# NanoFury16.net
KiCad netlist of a schematic drawn in Altium Designer
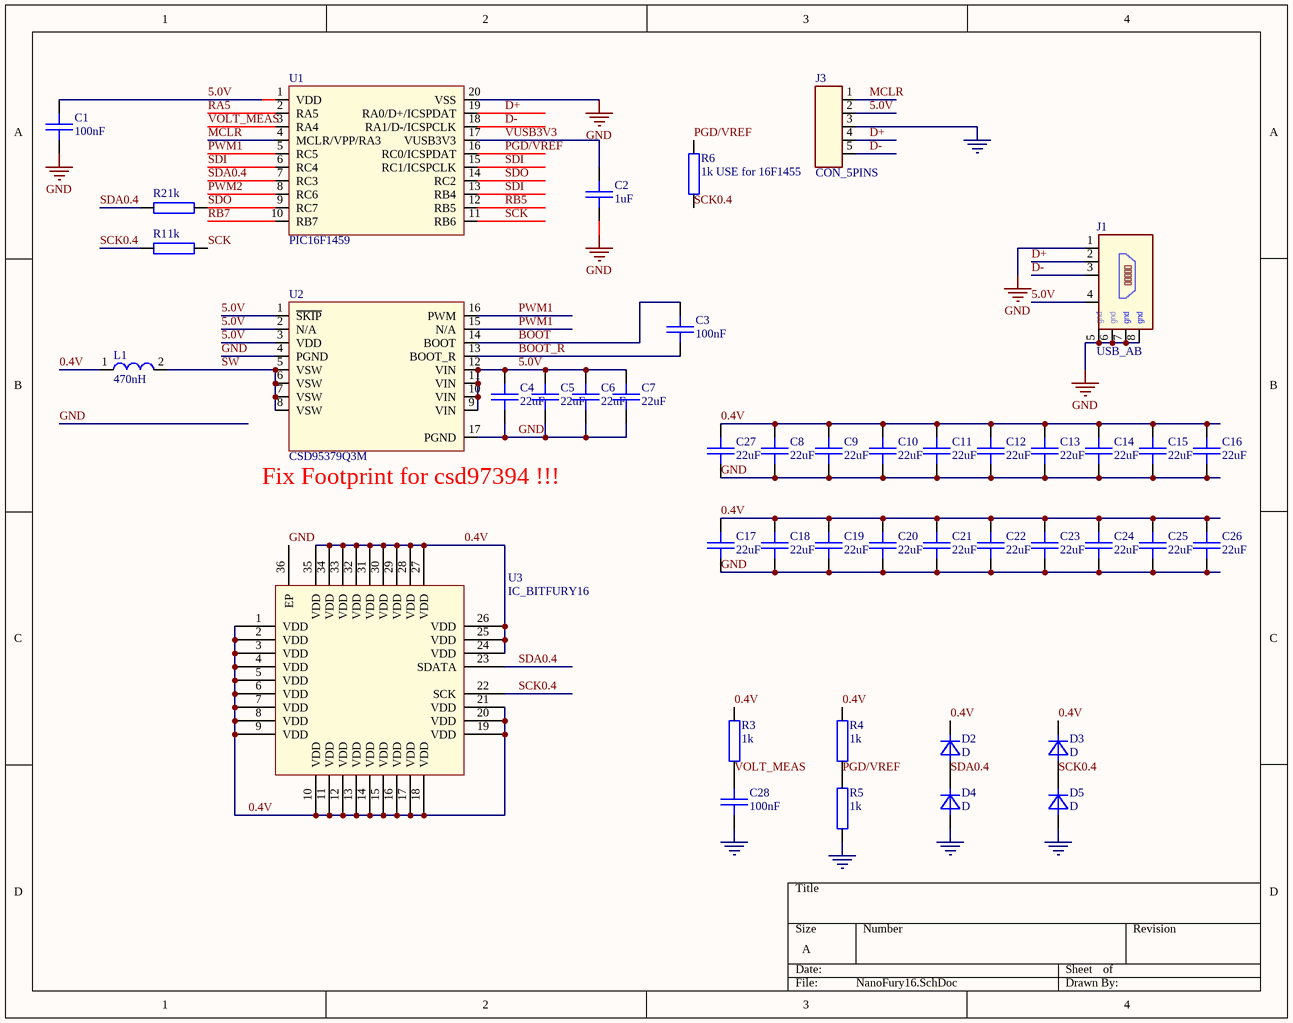
[diagram p0: NanoFury16.SchDoc]

(export (version "E")
  (design (tool "Eeschema 10.0.6"))
  (components
    (comp (ref "C1") (value "100nF") (footprint "SMD_0603_CAPC1608X95N") (libsource (lib "DLV") (part "C")))
    (comp (ref "C2") (value "1uF") (footprint "SMD_0603_CAPC1608X95N") (libsource (lib "DLV") (part "C")))
    (comp (ref "C3") (value "100nF") (footprint "SMD_0603_CAPC1608X95N") (libsource (lib "DLV") (part "C")))
    (comp (ref "C4") (value "22uF") (footprint "SMD_0805_CAPC2012X95N") (libsource (lib "DLV") (part "C")))
    (comp (ref "C5") (value "22uF") (footprint "SMD_0805_CAPC2012X95N") (libsource (lib "DLV") (part "C")))
    (comp (ref "C6") (value "22uF") (footprint "SMD_0805_CAPC2012X95N") (libsource (lib "DLV") (part "C")))
    (comp (ref "C7") (value "22uF") (footprint "SMD_0805_CAPC2012X95N") (libsource (lib "DLV") (part "C")))
    (comp (ref "C8") (value "22uF") (footprint "SMD_0805_CAPC2012X95N") (libsource (lib "DLV") (part "C")))
    (comp (ref "C9") (value "22uF") (footprint "SMD_0805_CAPC2012X95N") (libsource (lib "DLV") (part "C")))
    (comp (ref "C10") (value "22uF") (footprint "SMD_0805_CAPC2012X95N") (libsource (lib "DLV") (part "C")))
    (comp (ref "C11") (value "22uF") (footprint "SMD_0805_CAPC2012X95N") (libsource (lib "DLV") (part "C")))
    (comp (ref "C12") (value "22uF") (footprint "SMD_0805_CAPC2012X95N") (libsource (lib "DLV") (part "C")))
    (comp (ref "C13") (value "22uF") (footprint "SMD_0805_CAPC2012X95N") (libsource (lib "DLV") (part "C")))
    (comp (ref "C14") (value "22uF") (footprint "SMD_0805_CAPC2012X95N") (libsource (lib "DLV") (part "C")))
    (comp (ref "C15") (value "22uF") (footprint "SMD_0805_CAPC2012X95N") (libsource (lib "DLV") (part "C")))
    (comp (ref "C16") (value "22uF") (footprint "SMD_0805_CAPC2012X95N") (libsource (lib "DLV") (part "C")))
    (comp (ref "C17") (value "22uF") (footprint "SMD_0805_CAPC2012X95N") (libsource (lib "DLV") (part "C")))
    (comp (ref "C18") (value "22uF") (footprint "SMD_0805_CAPC2012X95N") (libsource (lib "DLV") (part "C")))
    (comp (ref "C19") (value "22uF") (footprint "SMD_0805_CAPC2012X95N") (libsource (lib "DLV") (part "C")))
    (comp (ref "C20") (value "22uF") (footprint "SMD_0805_CAPC2012X95N") (libsource (lib "DLV") (part "C")))
    (comp (ref "C21") (value "22uF") (footprint "SMD_0805_CAPC2012X95N") (libsource (lib "DLV") (part "C")))
    (comp (ref "C22") (value "22uF") (footprint "SMD_0805_CAPC2012X95N") (libsource (lib "DLV") (part "C")))
    (comp (ref "C23") (value "22uF") (footprint "SMD_0805_CAPC2012X95N") (libsource (lib "DLV") (part "C")))
    (comp (ref "C24") (value "22uF") (footprint "SMD_0805_CAPC2012X95N") (libsource (lib "DLV") (part "C")))
    (comp (ref "C25") (value "22uF") (footprint "SMD_0805_CAPC2012X95N") (libsource (lib "DLV") (part "C")))
    (comp (ref "C26") (value "22uF") (footprint "SMD_0805_CAPC2012X95N") (libsource (lib "DLV") (part "C")))
    (comp (ref "C27") (value "22uF") (footprint "SMD_0805_CAPC2012X95N") (libsource (lib "DLV") (part "C")))
    (comp (ref "C28") (value "100nF") (footprint "SMD_0603_CAPC1608X95N") (libsource (lib "DLV") (part "C")))
    (comp (ref "D2") (value "D") (footprint "SMD_SOD523_SOD1608X65N") (libsource (lib "DLV") (part "D")))
    (comp (ref "D3") (value "D") (footprint "SMD_SOD523_SOD1608X65N") (libsource (lib "DLV") (part "D")))
    (comp (ref "D4") (value "D") (footprint "SMD_SOD523_SOD1608X65N") (libsource (lib "DLV") (part "D")))
    (comp (ref "D5") (value "D") (footprint "SMD_SOD523_SOD1608X65N") (libsource (lib "DLV") (part "D")))
    (comp (ref "J1")
      (value "USB_AB")
      (footprint "PTH_CON_USB_FCI-87520-0010B-LF - MALE SMD PTH")
      (libsource (lib "DLV") (part "CON_USB_AB"))
    )
    (comp (ref "J3") (value "CON_5PINS") (footprint "SIP5 - PGM") (libsource (lib "DLV") (part "CON_5PINS")))
    (comp (ref "L1") (value "470nH") (footprint "SMD_INDM720X665X300") (libsource (lib "DLV") (part "L")))
    (comp (ref "R1") (value "1k") (footprint "SMD_0603_RESC1608X55N") (libsource (lib "DLV") (part "R")))
    (comp (ref "R2") (value "1k") (footprint "SMD_0603_RESC1608X55N") (libsource (lib "DLV") (part "R")))
    (comp (ref "R3") (value "1k") (footprint "SMD_0603_RESC1608X55N") (libsource (lib "DLV") (part "R")))
    (comp (ref "R4") (value "1k") (footprint "SMD_0603_RESC1608X55N") (libsource (lib "DLV") (part "R")))
    (comp (ref "R5") (value "1k") (footprint "SMD_0603_RESC1608X55N") (libsource (lib "DLV") (part "R")))
    (comp (ref "R6")
      (value "1k USE for 16F1455")
      (footprint "SMD_0603_RESC1608X55N")
      (libsource (lib "DLV") (part "R"))
    )
    (comp (ref "U1")
      (value "PIC16F1459")
      (footprint "SMD_SOP65P640X110-20N")
      (libsource (lib "DLV") (part "IC_PIC16F1459"))
    )
    (comp (ref "U2")
      (value "CSD95379Q3M")
      (footprint "SMD_SON50P340X340X80-21N - VSON10")
      (description "Texas Instrumendts Buck Boost DC-DC")
      (libsource (lib "DLV") (part "IC_CSD95379Q3M"))
    )
    (comp (ref "U3")
      (value "IC_BITFURY16")
      (footprint "SMD_QFN65P600X600X100-36AN")
      (description "BitFury 2016 16 nm")
      (libsource (lib "DLV") (part "IC_BITFURY16"))
    )
  )
  (nets
    (net (code "1") (name "/0.4V") (class "Default")
      (node (ref "C10") (pin "1") (pinfunction "1_1") (pintype "passive"))
      (node (ref "C11") (pin "1") (pinfunction "1_1") (pintype "passive"))
      (node (ref "C12") (pin "1") (pinfunction "1_1") (pintype "passive"))
      (node (ref "C13") (pin "1") (pinfunction "1_1") (pintype "passive"))
      (node (ref "C14") (pin "1") (pinfunction "1_1") (pintype "passive"))
      (node (ref "C15") (pin "1") (pinfunction "1_1") (pintype "passive"))
      (node (ref "C16") (pin "1") (pinfunction "1_1") (pintype "passive"))
      (node (ref "C17") (pin "1") (pinfunction "1_1") (pintype "passive"))
      (node (ref "C18") (pin "1") (pinfunction "1_1") (pintype "passive"))
      (node (ref "C19") (pin "1") (pinfunction "1_1") (pintype "passive"))
      (node (ref "C20") (pin "1") (pinfunction "1_1") (pintype "passive"))
      (node (ref "C21") (pin "1") (pinfunction "1_1") (pintype "passive"))
      (node (ref "C22") (pin "1") (pinfunction "1_1") (pintype "passive"))
      (node (ref "C23") (pin "1") (pinfunction "1_1") (pintype "passive"))
      (node (ref "C24") (pin "1") (pinfunction "1_1") (pintype "passive"))
      (node (ref "C25") (pin "1") (pinfunction "1_1") (pintype "passive"))
      (node (ref "C26") (pin "1") (pinfunction "1_1") (pintype "passive"))
      (node (ref "C27") (pin "1") (pinfunction "1_1") (pintype "passive"))
      (node (ref "C8") (pin "1") (pinfunction "1_1") (pintype "passive"))
      (node (ref "C9") (pin "1") (pinfunction "1_1") (pintype "passive"))
      (node (ref "D2") (pin "1") (pinfunction "C_1") (pintype "passive"))
      (node (ref "D3") (pin "1") (pinfunction "C_1") (pintype "passive"))
      (node (ref "L1") (pin "1") (pinfunction "1_1") (pintype "passive"))
      (node (ref "R3") (pin "1") (pinfunction "1_1") (pintype "passive"))
      (node (ref "R4") (pin "1") (pinfunction "1_1") (pintype "passive"))
      (node (ref "U3") (pin "1") (pinfunction "VDD_1") (pintype "passive"))
      (node (ref "U3") (pin "10") (pinfunction "VDD_10") (pintype "passive"))
      (node (ref "U3") (pin "11") (pinfunction "VDD_11") (pintype "passive"))
      (node (ref "U3") (pin "12") (pinfunction "VDD_12") (pintype "passive"))
      (node (ref "U3") (pin "13") (pinfunction "VDD_13") (pintype "passive"))
      (node (ref "U3") (pin "14") (pinfunction "VDD_14") (pintype "passive"))
      (node (ref "U3") (pin "15") (pinfunction "VDD_15") (pintype "passive"))
      (node (ref "U3") (pin "16") (pinfunction "VDD_16") (pintype "passive"))
      (node (ref "U3") (pin "17") (pinfunction "VDD_17") (pintype "passive"))
      (node (ref "U3") (pin "18") (pinfunction "VDD_18") (pintype "passive"))
      (node (ref "U3") (pin "19") (pinfunction "VDD_19") (pintype "passive"))
      (node (ref "U3") (pin "2") (pinfunction "VDD_2") (pintype "passive"))
      (node (ref "U3") (pin "20") (pinfunction "VDD_20") (pintype "passive"))
      (node (ref "U3") (pin "21") (pinfunction "VDD_21") (pintype "passive"))
      (node (ref "U3") (pin "24") (pinfunction "VDD_24") (pintype "passive"))
      (node (ref "U3") (pin "25") (pinfunction "VDD_25") (pintype "passive"))
      (node (ref "U3") (pin "26") (pinfunction "VDD_26") (pintype "passive"))
      (node (ref "U3") (pin "27") (pinfunction "VDD_27") (pintype "passive"))
      (node (ref "U3") (pin "28") (pinfunction "VDD_28") (pintype "passive"))
      (node (ref "U3") (pin "29") (pinfunction "VDD_29") (pintype "passive"))
      (node (ref "U3") (pin "3") (pinfunction "VDD_3") (pintype "passive"))
      (node (ref "U3") (pin "30") (pinfunction "VDD_30") (pintype "passive"))
      (node (ref "U3") (pin "31") (pinfunction "VDD_31") (pintype "passive"))
      (node (ref "U3") (pin "32") (pinfunction "VDD_32") (pintype "passive"))
      (node (ref "U3") (pin "33") (pinfunction "VDD_33") (pintype "passive"))
      (node (ref "U3") (pin "34") (pinfunction "VDD_34") (pintype "passive"))
      (node (ref "U3") (pin "35") (pinfunction "VDD_35") (pintype "passive"))
      (node (ref "U3") (pin "4") (pinfunction "VDD_4") (pintype "passive"))
      (node (ref "U3") (pin "5") (pinfunction "VDD_5") (pintype "passive"))
      (node (ref "U3") (pin "6") (pinfunction "VDD_6") (pintype "passive"))
      (node (ref "U3") (pin "7") (pinfunction "VDD_7") (pintype "passive"))
      (node (ref "U3") (pin "8") (pinfunction "VDD_8") (pintype "passive"))
      (node (ref "U3") (pin "9") (pinfunction "VDD_9") (pintype "passive"))
    )
    (net (code "2") (name "/5.0V") (class "Default")
      (node (ref "C1") (pin "1") (pinfunction "1_1") (pintype "passive"))
      (node (ref "C4") (pin "1") (pinfunction "1_1") (pintype "passive"))
      (node (ref "C5") (pin "1") (pinfunction "1_1") (pintype "passive"))
      (node (ref "C6") (pin "1") (pinfunction "1_1") (pintype "passive"))
      (node (ref "C7") (pin "1") (pinfunction "1_1") (pintype "passive"))
      (node (ref "J1") (pin "4") (pinfunction "4_4") (pintype "passive"))
      (node (ref "J3") (pin "2") (pinfunction "2_2") (pintype "passive"))
      (node (ref "U1") (pin "1") (pinfunction "VDD_1") (pintype "passive"))
      (node (ref "U2") (pin "1") (pinfunction "~{SKIP}_1") (pintype "passive"))
      (node (ref "U2") (pin "10") (pinfunction "VIN_10") (pintype "passive"))
      (node (ref "U2") (pin "11") (pinfunction "VIN_11") (pintype "passive"))
      (node (ref "U2") (pin "12") (pinfunction "VIN_12") (pintype "passive"))
      (node (ref "U2") (pin "2") (pinfunction "N/A_2") (pintype "passive"))
      (node (ref "U2") (pin "3") (pinfunction "VDD_3") (pintype "passive"))
      (node (ref "U2") (pin "9") (pinfunction "VIN_9") (pintype "passive"))
    )
    (net (code "3") (name "/BOOT") (class "Default")
      (node (ref "C3") (pin "1") (pinfunction "1_1") (pintype "passive"))
      (node (ref "U2") (pin "14") (pinfunction "BOOT_14") (pintype "passive"))
    )
    (net (code "4") (name "/BOOT_R") (class "Default")
      (node (ref "C3") (pin "2") (pinfunction "2_2") (pintype "passive"))
      (node (ref "U2") (pin "13") (pinfunction "BOOT_R_13") (pintype "passive"))
    )
    (net (code "5") (name "/D+") (class "Default")
      (node (ref "J1") (pin "2") (pinfunction "2_2") (pintype "passive"))
      (node (ref "J3") (pin "4") (pinfunction "4_4") (pintype "passive"))
      (node (ref "U1") (pin "19") (pinfunction "RA0/D+/ICSPDAT_19") (pintype "passive"))
    )
    (net (code "6") (name "/D-") (class "Default")
      (node (ref "J1") (pin "3") (pinfunction "3_3") (pintype "passive"))
      (node (ref "J3") (pin "5") (pinfunction "5_5") (pintype "passive"))
      (node (ref "U1") (pin "18") (pinfunction "RA1/D-/ICSPCLK_18") (pintype "passive"))
    )
    (net (code "7") (name "/MCLR") (class "Default")
      (node (ref "J3") (pin "1") (pinfunction "1_1") (pintype "passive"))
      (node (ref "U1") (pin "4") (pinfunction "MCLR/VPP/RA3_4") (pintype "passive"))
    )
    (net (code "8") (name "/PGD{slash}VREF") (class "Default")
      (node (ref "R4") (pin "2") (pinfunction "2_2") (pintype "passive"))
      (node (ref "R5") (pin "1") (pinfunction "1_1") (pintype "passive"))
      (node (ref "R6") (pin "1") (pinfunction "1_1") (pintype "passive"))
      (node (ref "U1") (pin "16") (pinfunction "RC0/ICSPDAT_16") (pintype "passive"))
    )
    (net (code "9") (name "/PWM1") (class "Default")
      (node (ref "U1") (pin "5") (pinfunction "RC5_5") (pintype "passive"))
      (node (ref "U2") (pin "15") (pinfunction "N/A_15") (pintype "passive"))
      (node (ref "U2") (pin "16") (pinfunction "PWM_16") (pintype "passive"))
    )
    (net (code "10") (name "/PWM2") (class "Default")
      (node (ref "U1") (pin "8") (pinfunction "RC6_8") (pintype "passive"))
    )
    (net (code "11") (name "/RA5") (class "Default")
      (node (ref "U1") (pin "2") (pinfunction "RA5_2") (pintype "passive"))
    )
    (net (code "12") (name "/RB5") (class "Default")
      (node (ref "U1") (pin "12") (pinfunction "RB5_12") (pintype "passive"))
    )
    (net (code "13") (name "/RB7") (class "Default")
      (node (ref "U1") (pin "10") (pinfunction "RB7_10") (pintype "passive"))
    )
    (net (code "14") (name "/SCK") (class "Default")
      (node (ref "R1") (pin "2") (pinfunction "2_2") (pintype "passive"))
      (node (ref "U1") (pin "11") (pinfunction "RB6_11") (pintype "passive"))
    )
    (net (code "15") (name "/SCK0.4") (class "Default")
      (node (ref "D3") (pin "2") (pinfunction "A_2") (pintype "passive"))
      (node (ref "D5") (pin "1") (pinfunction "C_1") (pintype "passive"))
      (node (ref "R1") (pin "1") (pinfunction "1_1") (pintype "passive"))
      (node (ref "R6") (pin "2") (pinfunction "2_2") (pintype "passive"))
      (node (ref "U3") (pin "22") (pinfunction "SCK_22") (pintype "passive"))
    )
    (net (code "16") (name "/SDA0.4") (class "Default")
      (node (ref "D2") (pin "2") (pinfunction "A_2") (pintype "passive"))
      (node (ref "D4") (pin "1") (pinfunction "C_1") (pintype "passive"))
      (node (ref "R2") (pin "2") (pinfunction "2_2") (pintype "passive"))
      (node (ref "U1") (pin "7") (pinfunction "RC3_7") (pintype "passive"))
      (node (ref "U3") (pin "23") (pinfunction "SDATA_23") (pintype "passive"))
    )
    (net (code "17") (name "/SDI") (class "Default")
      (node (ref "U1") (pin "13") (pinfunction "RB4_13") (pintype "passive"))
      (node (ref "U1") (pin "15") (pinfunction "RC1/ICSPCLK_15") (pintype "passive"))
      (node (ref "U1") (pin "6") (pinfunction "RC4_6") (pintype "passive"))
    )
    (net (code "18") (name "/SDO") (class "Default")
      (node (ref "R2") (pin "1") (pinfunction "1_1") (pintype "passive"))
      (node (ref "U1") (pin "14") (pinfunction "RC2_14") (pintype "passive"))
      (node (ref "U1") (pin "9") (pinfunction "RC7_9") (pintype "passive"))
    )
    (net (code "19") (name "/SW") (class "Default")
      (node (ref "L1") (pin "2") (pinfunction "2_2") (pintype "passive"))
      (node (ref "U2") (pin "5") (pinfunction "VSW_5") (pintype "passive"))
      (node (ref "U2") (pin "6") (pinfunction "VSW_6") (pintype "passive"))
      (node (ref "U2") (pin "7") (pinfunction "VSW_7") (pintype "passive"))
      (node (ref "U2") (pin "8") (pinfunction "VSW_8") (pintype "passive"))
    )
    (net (code "20") (name "/VOLT_MEAS") (class "Default")
      (node (ref "C28") (pin "1") (pinfunction "1_1") (pintype "passive"))
      (node (ref "R3") (pin "2") (pinfunction "2_2") (pintype "passive"))
      (node (ref "U1") (pin "3") (pinfunction "RA4_3") (pintype "passive"))
    )
    (net (code "21") (name "/VUSB3V3") (class "Default")
      (node (ref "C2") (pin "1") (pinfunction "1_1") (pintype "passive"))
      (node (ref "U1") (pin "17") (pinfunction "VUSB3V3_17") (pintype "passive"))
    )
    (net (code "22") (name "GND") (class "Default")
      (node (ref "C1") (pin "2") (pinfunction "2_2") (pintype "passive"))
      (node (ref "C10") (pin "2") (pinfunction "2_2") (pintype "passive"))
      (node (ref "C11") (pin "2") (pinfunction "2_2") (pintype "passive"))
      (node (ref "C12") (pin "2") (pinfunction "2_2") (pintype "passive"))
      (node (ref "C13") (pin "2") (pinfunction "2_2") (pintype "passive"))
      (node (ref "C14") (pin "2") (pinfunction "2_2") (pintype "passive"))
      (node (ref "C15") (pin "2") (pinfunction "2_2") (pintype "passive"))
      (node (ref "C16") (pin "2") (pinfunction "2_2") (pintype "passive"))
      (node (ref "C17") (pin "2") (pinfunction "2_2") (pintype "passive"))
      (node (ref "C18") (pin "2") (pinfunction "2_2") (pintype "passive"))
      (node (ref "C19") (pin "2") (pinfunction "2_2") (pintype "passive"))
      (node (ref "C2") (pin "2") (pinfunction "2_2") (pintype "passive"))
      (node (ref "C20") (pin "2") (pinfunction "2_2") (pintype "passive"))
      (node (ref "C21") (pin "2") (pinfunction "2_2") (pintype "passive"))
      (node (ref "C22") (pin "2") (pinfunction "2_2") (pintype "passive"))
      (node (ref "C23") (pin "2") (pinfunction "2_2") (pintype "passive"))
      (node (ref "C24") (pin "2") (pinfunction "2_2") (pintype "passive"))
      (node (ref "C25") (pin "2") (pinfunction "2_2") (pintype "passive"))
      (node (ref "C26") (pin "2") (pinfunction "2_2") (pintype "passive"))
      (node (ref "C27") (pin "2") (pinfunction "2_2") (pintype "passive"))
      (node (ref "C28") (pin "2") (pinfunction "2_2") (pintype "passive"))
      (node (ref "C4") (pin "2") (pinfunction "2_2") (pintype "passive"))
      (node (ref "C5") (pin "2") (pinfunction "2_2") (pintype "passive"))
      (node (ref "C6") (pin "2") (pinfunction "2_2") (pintype "passive"))
      (node (ref "C7") (pin "2") (pinfunction "2_2") (pintype "passive"))
      (node (ref "C8") (pin "2") (pinfunction "2_2") (pintype "passive"))
      (node (ref "C9") (pin "2") (pinfunction "2_2") (pintype "passive"))
      (node (ref "D4") (pin "2") (pinfunction "A_2") (pintype "passive"))
      (node (ref "D5") (pin "2") (pinfunction "A_2") (pintype "passive"))
      (node (ref "J1") (pin "1") (pinfunction "1_1") (pintype "passive"))
      (node (ref "J1") (pin "5") (pinfunction "5_5") (pintype "passive"))
      (node (ref "J1") (pin "6") (pinfunction "6_6") (pintype "passive"))
      (node (ref "J1") (pin "7") (pinfunction "7_7") (pintype "passive"))
      (node (ref "J1") (pin "8") (pinfunction "8_8") (pintype "passive"))
      (node (ref "J3") (pin "3") (pinfunction "3_3") (pintype "passive"))
      (node (ref "R5") (pin "2") (pinfunction "2_2") (pintype "passive"))
      (node (ref "U1") (pin "20") (pinfunction "VSS_20") (pintype "passive"))
      (node (ref "U2") (pin "17") (pinfunction "PGND_17") (pintype "passive"))
      (node (ref "U2") (pin "4") (pinfunction "PGND_4") (pintype "passive"))
      (node (ref "U3") (pin "36") (pinfunction "EP_36") (pintype "passive"))
    )
  )
)
